# untitled2.net
KiCad netlist of a schematic drawn in EAGLE
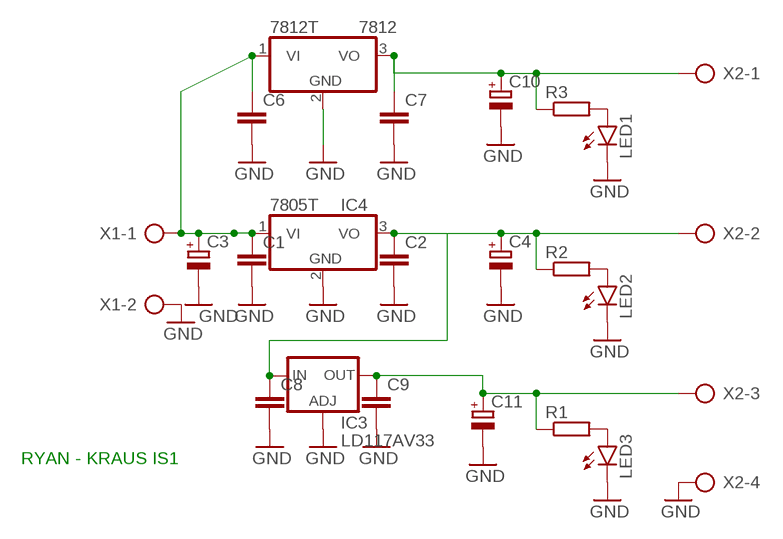
[diagram p0: schematic, sheet 1]

(export (version "E")
  (design (tool "Eeschema 10.0.6"))
  (components
    (comp (ref "7812")
      (value "7812T")
      (footprint "eagle-import:TO220H")
      (libsource (lib "eagle-import") (part "78T12"))
    )
    (comp (ref "C1")
      (value "C-EU050-025X075")
      (footprint "eagle-import:C050-025X075")
      (libsource (lib "eagle-import") (part "C-EU050-025X075"))
    )
    (comp (ref "C2")
      (value "C-EU050-025X075")
      (footprint "eagle-import:C050-025X075")
      (libsource (lib "eagle-import") (part "C-EU050-025X075"))
    )
    (comp (ref "C3")
      (value "CPOL-EUE5-13")
      (footprint "eagle-import:E5-13")
      (libsource (lib "eagle-import") (part "CPOL-EUE5-13"))
    )
    (comp (ref "C4")
      (value "CPOL-EUE5-6")
      (footprint "eagle-import:E5-6")
      (libsource (lib "eagle-import") (part "CPOL-EUE5-6"))
    )
    (comp (ref "C6")
      (value "C-EU050-025X075")
      (footprint "eagle-import:C050-025X075")
      (libsource (lib "eagle-import") (part "C-EU050-025X075"))
    )
    (comp (ref "C7")
      (value "C-EU050-025X075")
      (footprint "eagle-import:C050-025X075")
      (libsource (lib "eagle-import") (part "C-EU050-025X075"))
    )
    (comp (ref "C8")
      (value "C-EU050-025X075")
      (footprint "eagle-import:C050-025X075")
      (libsource (lib "eagle-import") (part "C-EU050-025X075"))
    )
    (comp (ref "C9")
      (value "C-EU050-025X075")
      (footprint "eagle-import:C050-025X075")
      (libsource (lib "eagle-import") (part "C-EU050-025X075"))
    )
    (comp (ref "C10")
      (value "CPOL-EUE5-6")
      (footprint "eagle-import:E5-6")
      (libsource (lib "eagle-import") (part "CPOL-EUE5-6"))
    )
    (comp (ref "C11")
      (value "CPOL-EUE5-6")
      (footprint "eagle-import:E5-6")
      (libsource (lib "eagle-import") (part "CPOL-EUE5-6"))
    )
    (comp (ref "IC3")
      (value "LD117AV33")
      (footprint "eagle-import:TO220L1")
      (libsource (lib "eagle-import") (part "LD117A?V33"))
    )
    (comp (ref "IC4")
      (value "7805T")
      (footprint "eagle-import:TO220H")
      (libsource (lib "eagle-import") (part "78T05"))
    )
    (comp (ref "LED1")
      (value "LED5MM")
      (footprint "eagle-import:LED5MM")
      (libsource (lib "eagle-import") (part "LED5MM"))
    )
    (comp (ref "LED2")
      (value "LED5MM")
      (footprint "eagle-import:LED5MM")
      (libsource (lib "eagle-import") (part "LED5MM"))
    )
    (comp (ref "LED3")
      (value "LED5MM")
      (footprint "eagle-import:LED5MM")
      (libsource (lib "eagle-import") (part "LED5MM"))
    )
    (comp (ref "R1")
      (value "R-EU_0204/7")
      (footprint "eagle-import:0204_7")
      (libsource (lib "eagle-import") (part "R-EU_0204/7"))
    )
    (comp (ref "R2")
      (value "R-EU_0204/7")
      (footprint "eagle-import:0204_7")
      (libsource (lib "eagle-import") (part "R-EU_0204/7"))
    )
    (comp (ref "R3")
      (value "R-EU_0204/7")
      (footprint "eagle-import:0204_7")
      (libsource (lib "eagle-import") (part "R-EU_0204/7"))
    )
    (comp (ref "X1")
      (value "AK300/2")
      (footprint "eagle-import:AK300_2")
      (libsource (lib "eagle-import") (part "AK300/2"))
    )
    (comp (ref "X2")
      (value "AK300/4")
      (footprint "eagle-import:AK300_4")
      (libsource (lib "eagle-import") (part "AK300/4"))
    )
  )
  (nets
    (net (code "1") (name "GND") (class "Default")
      (node (ref "7812") (pin "2") (pinfunction "GND_2") (pintype "passive"))
      (node (ref "C1") (pin "2") (pinfunction "2_2") (pintype "passive"))
      (node (ref "C10") (pin "-") (pinfunction "-_-") (pintype "passive"))
      (node (ref "C11") (pin "-") (pinfunction "-_-") (pintype "passive"))
      (node (ref "C2") (pin "2") (pinfunction "2_2") (pintype "passive"))
      (node (ref "C3") (pin "-") (pinfunction "-_-") (pintype "passive"))
      (node (ref "C4") (pin "-") (pinfunction "-_-") (pintype "passive"))
      (node (ref "C6") (pin "2") (pinfunction "2_2") (pintype "passive"))
      (node (ref "C7") (pin "2") (pinfunction "2_2") (pintype "passive"))
      (node (ref "C8") (pin "2") (pinfunction "2_2") (pintype "passive"))
      (node (ref "C9") (pin "2") (pinfunction "2_2") (pintype "passive"))
      (node (ref "IC3") (pin "1") (pinfunction "ADJ_1") (pintype "input"))
      (node (ref "IC4") (pin "2") (pinfunction "GND_2") (pintype "passive"))
      (node (ref "LED1") (pin "K") (pinfunction "C_K") (pintype "passive"))
      (node (ref "LED2") (pin "K") (pinfunction "C_K") (pintype "passive"))
      (node (ref "LED3") (pin "K") (pinfunction "C_K") (pintype "passive"))
      (node (ref "X1") (pin "2") (pinfunction "KL_2") (pintype "passive"))
      (node (ref "X2") (pin "4") (pinfunction "KL_4") (pintype "passive"))
    )
    (net (code "2") (name "Net-(7812-VI)") (class "Default")
      (node (ref "7812") (pin "1") (pinfunction "VI_1") (pintype "input"))
      (node (ref "C1") (pin "1") (pinfunction "1_1") (pintype "passive"))
      (node (ref "C3") (pin "+") (pinfunction "+_+") (pintype "passive"))
      (node (ref "C6") (pin "1") (pinfunction "1_1") (pintype "passive"))
      (node (ref "IC4") (pin "1") (pinfunction "VI_1") (pintype "input"))
      (node (ref "X1") (pin "1") (pinfunction "KL_1") (pintype "passive"))
    )
    (net (code "3") (name "Net-(7812-VO)") (class "Default")
      (node (ref "7812") (pin "3") (pinfunction "VO_3") (pintype "passive"))
      (node (ref "C10") (pin "+") (pinfunction "+_+") (pintype "passive"))
      (node (ref "C7") (pin "1") (pinfunction "1_1") (pintype "passive"))
      (node (ref "R3") (pin "1") (pinfunction "1_1") (pintype "passive"))
      (node (ref "X2") (pin "1") (pinfunction "KL_1") (pintype "passive"))
    )
    (net (code "4") (name "Net-(IC3-IN)") (class "Default")
      (node (ref "C2") (pin "1") (pinfunction "1_1") (pintype "passive"))
      (node (ref "C4") (pin "+") (pinfunction "+_+") (pintype "passive"))
      (node (ref "C8") (pin "1") (pinfunction "1_1") (pintype "passive"))
      (node (ref "IC3") (pin "3") (pinfunction "IN_3") (pintype "input"))
      (node (ref "IC4") (pin "3") (pinfunction "VO_3") (pintype "passive"))
      (node (ref "R2") (pin "1") (pinfunction "1_1") (pintype "passive"))
      (node (ref "X2") (pin "2") (pinfunction "KL_2") (pintype "passive"))
    )
    (net (code "5") (name "Net-(IC3-OUT)") (class "Default")
      (node (ref "C11") (pin "+") (pinfunction "+_+") (pintype "passive"))
      (node (ref "C9") (pin "1") (pinfunction "1_1") (pintype "passive"))
      (node (ref "IC3") (pin "2") (pinfunction "OUT_2") (pintype "passive"))
      (node (ref "R1") (pin "1") (pinfunction "1_1") (pintype "passive"))
      (node (ref "X2") (pin "3") (pinfunction "KL_3") (pintype "passive"))
    )
    (net (code "6") (name "Net-(LED1-PadA)") (class "Default")
      (node (ref "LED1") (pin "A") (pinfunction "A_A") (pintype "passive"))
      (node (ref "R3") (pin "2") (pinfunction "2_2") (pintype "passive"))
    )
    (net (code "7") (name "Net-(LED2-PadA)") (class "Default")
      (node (ref "LED2") (pin "A") (pinfunction "A_A") (pintype "passive"))
      (node (ref "R2") (pin "2") (pinfunction "2_2") (pintype "passive"))
    )
    (net (code "8") (name "Net-(LED3-PadA)") (class "Default")
      (node (ref "LED3") (pin "A") (pinfunction "A_A") (pintype "passive"))
      (node (ref "R1") (pin "2") (pinfunction "2_2") (pintype "passive"))
    )
  )
)
